# ATtinyProgrammer.net
KiCad netlist of a schematic drawn in EAGLE
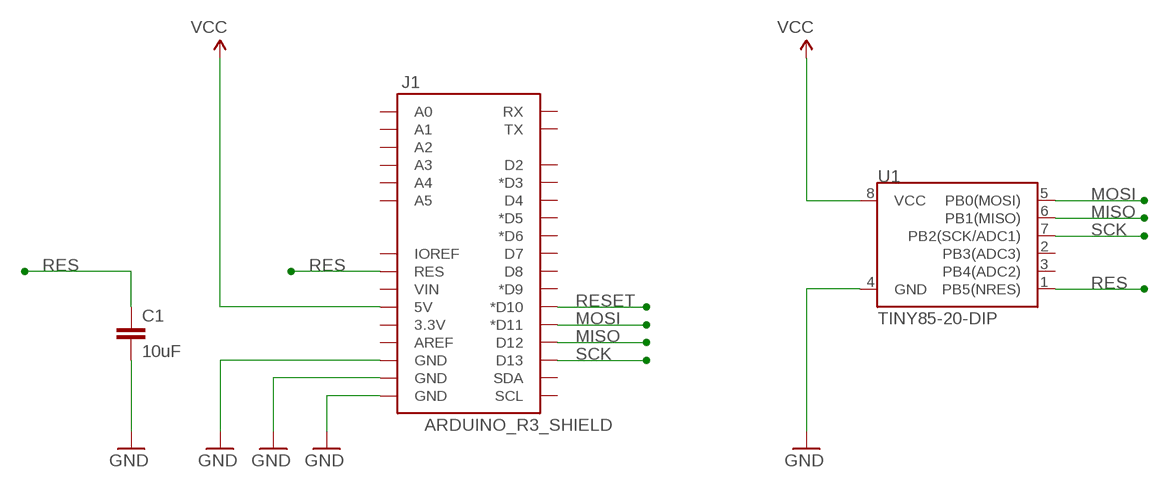
[diagram p0: schematic, sheet 1]

(export (version "E")
  (design (tool "Eeschema 10.0.6"))
  (components
    (comp (ref "C1")
      (value "10uF")
      (footprint "eagle-import:CAP-PTH-SMALL-KIT")
      (libsource (lib "eagle-import") (part "0.1UF-50V-20%(PTH)KIT-EZ"))
    )
    (comp (ref "J1")
      (value "ARDUINO_R3_SHIELD")
      (footprint "eagle-import:UNO_R3_SHIELD")
      (libsource (lib "eagle-import") (part "ARDUINO_R3_SHIELD"))
    )
    (comp (ref "U1")
      (value "TINY85-20-DIP")
      (footprint "eagle-import:DIP08")
      (libsource (lib "eagle-import") (part "ATTINY45TINY85-20-DIP"))
    )
  )
  (nets
    (net (code "1") (name "/MISO") (class "Default")
      (node (ref "J1") (pin "D12") (pinfunction "D12_D12") (pintype "bidirectional"))
      (node (ref "U1") (pin "6") (pinfunction "PB1(MISO)_6") (pintype "bidirectional"))
    )
    (net (code "2") (name "/MOSI") (class "Default")
      (node (ref "J1") (pin "D11") (pinfunction "*D11_D11") (pintype "bidirectional"))
      (node (ref "U1") (pin "5") (pinfunction "PB0(MOSI)_5") (pintype "bidirectional"))
    )
    (net (code "3") (name "/RES") (class "Default")
      (node (ref "C1") (pin "1") (pinfunction "1_1") (pintype "passive"))
      (node (ref "J1") (pin "RES") (pinfunction "RES_RES") (pintype "bidirectional"))
      (node (ref "U1") (pin "1") (pinfunction "PB5(NRES)_1") (pintype "bidirectional"))
    )
    (net (code "4") (name "/RESET") (class "Default")
      (node (ref "J1") (pin "D10") (pinfunction "*D10_D10") (pintype "bidirectional"))
    )
    (net (code "5") (name "/SCK") (class "Default")
      (node (ref "J1") (pin "D13") (pinfunction "D13_D13") (pintype "bidirectional"))
      (node (ref "U1") (pin "7") (pinfunction "PB2(SCK/ADC1)_7") (pintype "bidirectional"))
    )
    (net (code "6") (name "GND") (class "Default")
      (node (ref "C1") (pin "2") (pinfunction "2_2") (pintype "passive"))
      (node (ref "J1") (pin "GND@0") (pinfunction "GND_GND@0") (pintype "bidirectional"))
      (node (ref "J1") (pin "GND@1") (pinfunction "GND_GND@1") (pintype "bidirectional"))
      (node (ref "J1") (pin "GND@2") (pinfunction "GND_GND@2") (pintype "bidirectional"))
      (node (ref "U1") (pin "4") (pinfunction "GND_4") (pintype "bidirectional"))
    )
    (net (code "7") (name "VCC") (class "Default")
      (node (ref "J1") (pin "5V") (pinfunction "5V_5V") (pintype "bidirectional"))
      (node (ref "U1") (pin "8") (pinfunction "VCC_8") (pintype "bidirectional"))
    )
    (net (code "8") (name "unconnected-(J1-*D3-PadD3)") (class "Default")
      (node (ref "J1") (pin "D3") (pinfunction "*D3_D3") (pintype "bidirectional"))
    )
    (net (code "9") (name "unconnected-(J1-*D5-PadD5)") (class "Default")
      (node (ref "J1") (pin "D5") (pinfunction "*D5_D5") (pintype "bidirectional"))
    )
    (net (code "10") (name "unconnected-(J1-*D6-PadD6)") (class "Default")
      (node (ref "J1") (pin "D6") (pinfunction "*D6_D6") (pintype "bidirectional"))
    )
    (net (code "11") (name "unconnected-(J1-*D9-PadD9)") (class "Default")
      (node (ref "J1") (pin "D9") (pinfunction "*D9_D9") (pintype "bidirectional"))
    )
    (net (code "12") (name "unconnected-(J1-Pad3.3V)") (class "Default")
      (node (ref "J1") (pin "3.3V") (pinfunction "3.3V_3.3V") (pintype "bidirectional"))
    )
    (net (code "13") (name "unconnected-(J1-PadA0)") (class "Default")
      (node (ref "J1") (pin "A0") (pinfunction "A0_A0") (pintype "bidirectional"))
    )
    (net (code "14") (name "unconnected-(J1-PadA1)") (class "Default")
      (node (ref "J1") (pin "A1") (pinfunction "A1_A1") (pintype "bidirectional"))
    )
    (net (code "15") (name "unconnected-(J1-PadA2)") (class "Default")
      (node (ref "J1") (pin "A2") (pinfunction "A2_A2") (pintype "bidirectional"))
    )
    (net (code "16") (name "unconnected-(J1-PadA3)") (class "Default")
      (node (ref "J1") (pin "A3") (pinfunction "A3_A3") (pintype "bidirectional"))
    )
    (net (code "17") (name "unconnected-(J1-PadA4)") (class "Default")
      (node (ref "J1") (pin "A4") (pinfunction "A4_A4") (pintype "bidirectional"))
    )
    (net (code "18") (name "unconnected-(J1-PadA5)") (class "Default")
      (node (ref "J1") (pin "A5") (pinfunction "A5_A5") (pintype "bidirectional"))
    )
    (net (code "19") (name "unconnected-(J1-PadAREF)") (class "Default")
      (node (ref "J1") (pin "AREF") (pinfunction "AREF_AREF") (pintype "bidirectional"))
    )
    (net (code "20") (name "unconnected-(J1-PadD2)") (class "Default")
      (node (ref "J1") (pin "D2") (pinfunction "D2_D2") (pintype "bidirectional"))
    )
    (net (code "21") (name "unconnected-(J1-PadD4)") (class "Default")
      (node (ref "J1") (pin "D4") (pinfunction "D4_D4") (pintype "bidirectional"))
    )
    (net (code "22") (name "unconnected-(J1-PadD7)") (class "Default")
      (node (ref "J1") (pin "D7") (pinfunction "D7_D7") (pintype "bidirectional"))
    )
    (net (code "23") (name "unconnected-(J1-PadD8)") (class "Default")
      (node (ref "J1") (pin "D8") (pinfunction "D8_D8") (pintype "bidirectional"))
    )
    (net (code "24") (name "unconnected-(J1-PadIOREF)") (class "Default")
      (node (ref "J1") (pin "IOREF") (pinfunction "IOREF_IOREF") (pintype "bidirectional"))
    )
    (net (code "25") (name "unconnected-(J1-PadRX)") (class "Default")
      (node (ref "J1") (pin "RX") (pinfunction "RX_RX") (pintype "bidirectional"))
    )
    (net (code "26") (name "unconnected-(J1-PadSCL)") (class "Default")
      (node (ref "J1") (pin "SCL") (pinfunction "SCL_SCL") (pintype "bidirectional"))
    )
    (net (code "27") (name "unconnected-(J1-PadSDA)") (class "Default")
      (node (ref "J1") (pin "SDA") (pinfunction "SDA_SDA") (pintype "bidirectional"))
    )
    (net (code "28") (name "unconnected-(J1-PadTX)") (class "Default")
      (node (ref "J1") (pin "TX") (pinfunction "TX_TX") (pintype "bidirectional"))
    )
    (net (code "29") (name "unconnected-(J1-PadVIN)") (class "Default")
      (node (ref "J1") (pin "VIN") (pinfunction "VIN_VIN") (pintype "bidirectional"))
    )
    (net (code "30") (name "unconnected-(U1-PB3(ADC3)-Pad2)") (class "Default")
      (node (ref "U1") (pin "2") (pinfunction "PB3(ADC3)_2") (pintype "bidirectional"))
    )
    (net (code "31") (name "unconnected-(U1-PB4(ADC2)-Pad3)") (class "Default")
      (node (ref "U1") (pin "3") (pinfunction "PB4(ADC2)_3") (pintype "bidirectional"))
    )
  )
)
